# TINY1616.net
KiCad netlist of a schematic drawn in Altium Designer
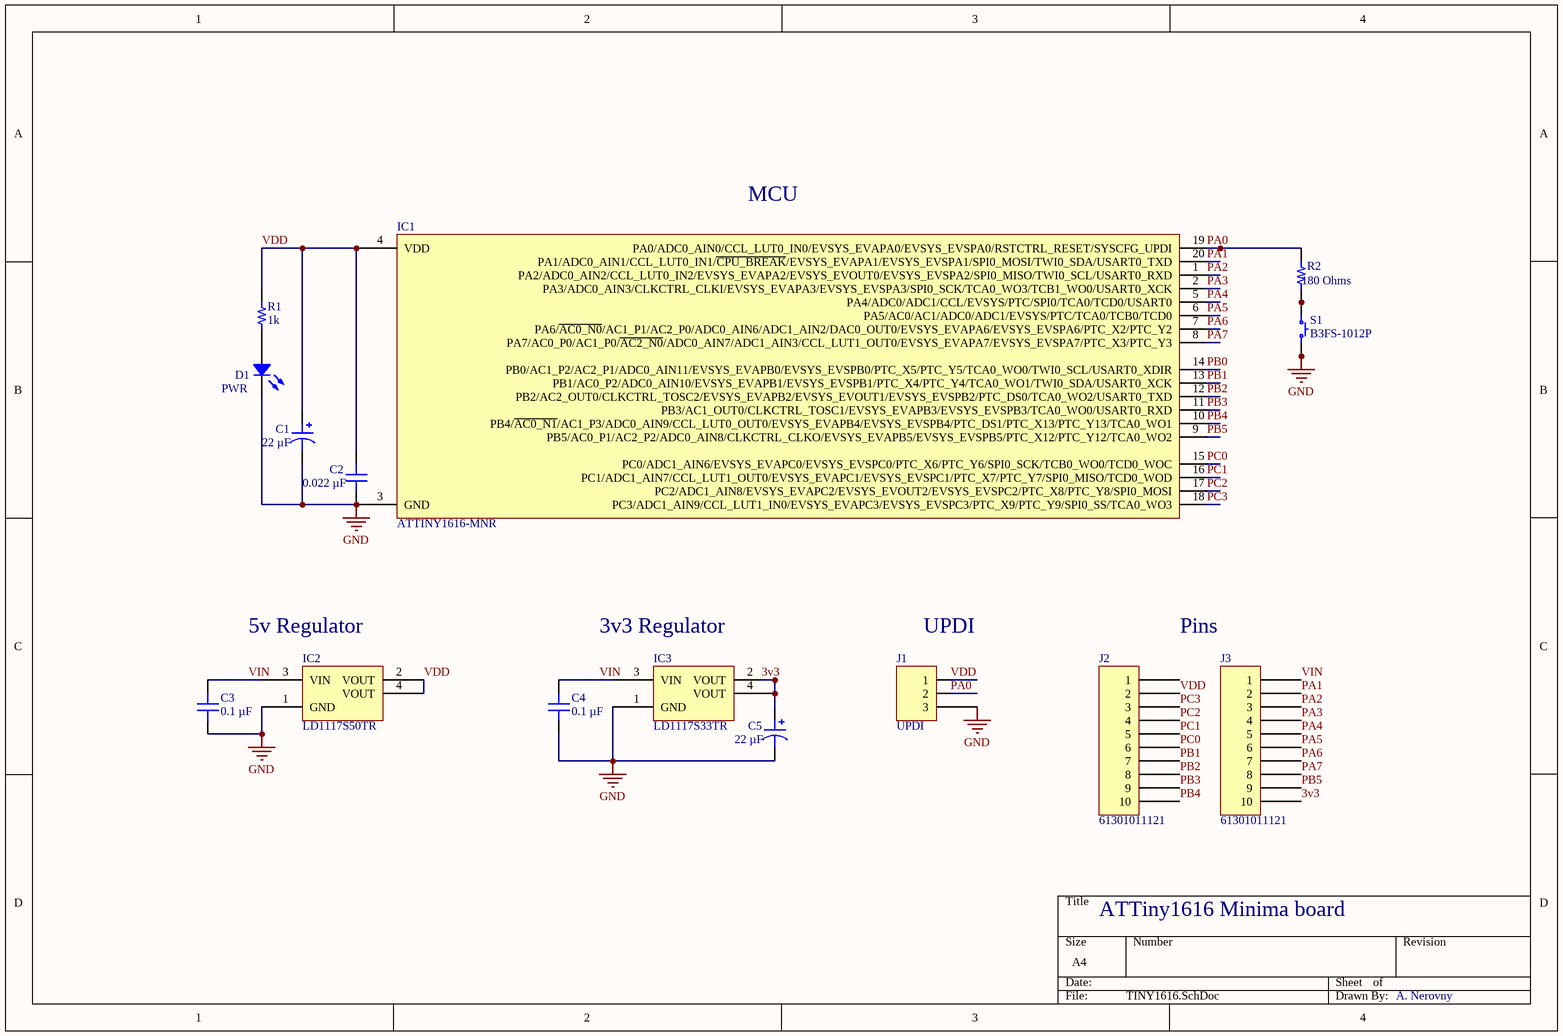
[diagram p0: TINY1616.SchDoc]

(export (version "E")
  (design (tool "Eeschema 10.0.6"))
  (components
    (comp (ref "C1")
      (value "22 µF")
      (footprint "CAP POL 1206_3216")
      (description "293D105X9016A8T")
      (fields (field (name "MANUFACTURER") "Vishay Sprague") (field (name "TOLERANCE") "±10%"))
      (libsource (lib "Celestial Altium Library - altium_library") (part "Polarised Capacitor"))
    )
    (comp (ref "C2")
      (value "0.022 µF")
      (footprint "CAP 0402_1005")
      (description "CAP CER 0402 22NF 50V X7R 10%")
      (fields
        (field (name "PART NUMBER") "C0402C223K5RECAUTO")
        (field (name "CAPACITANCE") "0.022 µF")
        (field (name "MANUFACTURER") "KEMET")
      )
      (libsource (lib "Celestial Altium Library - altium_library") (part "Capacitor"))
    )
    (comp (ref "C3")
      (value "0.1 µF")
      (footprint "CAP 0603_1608")
      (description "CAP CER 0.1UF 50V X7R 0603")
      (fields
        (field (name "PART NUMBER") "C0603C104K5RAC7411")
        (field (name "CAPACITANCE") "0.1 µF")
        (field (name "MANUFACTURER") "KEMET")
      )
      (libsource (lib "Celestial Altium Library - altium_library") (part "Capacitor"))
    )
    (comp (ref "C4")
      (value "0.1 µF")
      (footprint "CAP 0603_1608")
      (description "CAP CER 0.1UF 50V X7R 0603")
      (fields
        (field (name "PART NUMBER") "C0603C104K5RAC7411")
        (field (name "CAPACITANCE") "0.1 µF")
        (field (name "MANUFACTURER") "KEMET")
      )
      (libsource (lib "Celestial Altium Library - altium_library") (part "Capacitor"))
    )
    (comp (ref "C5")
      (value "22 µF")
      (footprint "CAP POL 1206_3216")
      (description "293D105X9016A8T")
      (fields (field (name "MANUFACTURER") "Vishay Sprague") (field (name "TOLERANCE") "±10%"))
      (libsource (lib "Celestial Altium Library - altium_library") (part "Polarised Capacitor"))
    )
    (comp (ref "D1")
      (value "PWR")
      (footprint "LED 0805_2012 GREEN")
      (description "LED GREEN CLEAR 0805 SMD")
      (fields
        (field (name "PART NUMBER") "QTLP630C4TR")
        (field (name "MANUFACTURER") "Everlight Electronics Co Ltd")
      )
      (libsource (lib "Celestial Altium Library - altium_library") (part "LED"))
    )
    (comp (ref "IC1")
      (value "ATTINY1616-MNR")
      (footprint "MICROCHIP VQFN-20 3X3 REB")
      (description "IC MCU 8BIT 16KB FLASH 20VQFN")
      (fields (field (name "MANUFACTURER") "Microchip Technology"))
      (libsource (lib "Celestial Altium Library - altium_library") (part "MICROCHIP ATTINY1616-MNR VQFN20"))
    )
    (comp (ref "IC2")
      (value "LD1117S50TR")
      (footprint "ST SOT-223")
      (description "IC REG LINEAR 5V 800MA SOT223")
      (fields (field (name "MANUFACTURER") "STMicroelectronics"))
      (libsource (lib "Celestial Altium Library - altium_library") (part "ST LD1117"))
    )
    (comp (ref "IC3")
      (value "LD1117S33TR")
      (footprint "ST SOT-223")
      (description "IC REG LINEAR 3.3V 800MA SOT223")
      (fields (field (name "MANUFACTURER") "STMicroelectronics"))
      (libsource (lib "Celestial Altium Library - altium_library") (part "ST LD1117"))
    )
    (comp (ref "J1")
      (value "UPDI")
      (footprint "WURTH WE-PHD 61300311121")
      (description "CONN HEADER VERT 3POS 2.54MM")
      (fields (field (name "PART NUMBER") "61300311121") (field (name "MANUFACTURER") "Würth Elektronik"))
      (libsource (lib "Celestial Altium Library - altium_library") (part "3 Pin"))
    )
    (comp (ref "J2")
      (value "61301011121")
      (footprint "WURTH WE-PHD 61301011121")
      (description "CONN HEADER VERT 10POS 2.54MM")
      (fields (field (name "MANUFACTURER") "Würth Elektronik"))
      (libsource (lib "Celestial Altium Library - altium_library") (part "10 Pin"))
    )
    (comp (ref "J3")
      (value "61301011121")
      (footprint "WURTH WE-PHD 61301011121")
      (description "CONN HEADER VERT 10POS 2.54MM")
      (fields (field (name "MANUFACTURER") "Würth Elektronik"))
      (libsource (lib "Celestial Altium Library - altium_library") (part "10 Pin"))
    )
    (comp (ref "R1")
      (value "1k")
      (footprint "RES 0402_1005")
      (description "RES 1K OHM 1% 1/5W 0402")
      (fields (field (name "PART NUMBER") "RCA04021K00FKEDHP") (field (name "MANUFACTURER") "Vishay Dale"))
      (libsource (lib "Celestial Altium Library - altium_library") (part "Resistor"))
    )
    (comp (ref "R2")
      (value "180 Ohms")
      (footprint "RES 0603_1608")
      (description "RES SMD 180 OHM 5% 1/10W 0603")
      (fields (field (name "PART NUMBER") "CRCW0603180RJNEA") (field (name "MANUFACTURER") "Vishay Dale"))
      (libsource (lib "Celestial Altium Library - altium_library") (part "Resistor"))
    )
    (comp (ref "S1")
      (value "B3FS-1012P")
      (footprint "OMRON B3FS-1012P")
      (description "SWITCH TACTILE SPST-NO 0.05A 24V")
      (fields (field (name "MANUFACTURER") "Omron Electronics Inc-EMC Div"))
      (libsource (lib "Celestial Altium Library - altium_library") (part "SPST-NO 4 PIN"))
    )
  )
  (nets
    (net (code "1") (name "/3v3") (class "Default")
      (node (ref "C5") (pin "1") (pinfunction "1_1") (pintype "passive"))
      (node (ref "IC3") (pin "2") (pinfunction "VOUT_2") (pintype "passive"))
      (node (ref "IC3") (pin "4") (pinfunction "VOUT_4") (pintype "passive"))
      (node (ref "J3") (pin "10") (pinfunction "10_10") (pintype "passive"))
    )
    (net (code "2") (name "/PA0") (class "Default")
      (node (ref "IC1") (pin "19") (pinfunction "PA0/ADC0_AIN0/CCL_LUT0_IN0/EVSYS_EVAPA0/EVSYS_EVSPA0/RSTCTRL_RESET/SYSCFG_UPDI_19") (pintype "passive"))
      (node (ref "J1") (pin "2") (pinfunction "2_2") (pintype "passive"))
      (node (ref "R2") (pin "2") (pinfunction "2_2") (pintype "passive"))
    )
    (net (code "3") (name "/PA1") (class "Default")
      (node (ref "IC1") (pin "20") (pinfunction "PA1/ADC0_AIN1/CCL_LUT0_IN1/~{CPU_BREAK}/EVSYS_EVAPA1/EVSYS_EVSPA1/SPI0_MOSI/TWI0_SDA/USART0_TXD_20") (pintype "passive"))
      (node (ref "J3") (pin "2") (pinfunction "2_2") (pintype "passive"))
    )
    (net (code "4") (name "/PA2") (class "Default")
      (node (ref "IC1") (pin "1") (pinfunction "PA2/ADC0_AIN2/CCL_LUT0_IN2/EVSYS_EVAPA2/EVSYS_EVOUT0/EVSYS_EVSPA2/SPI0_MISO/TWI0_SCL/USART0_RXD_1") (pintype "passive"))
      (node (ref "J3") (pin "3") (pinfunction "3_3") (pintype "passive"))
    )
    (net (code "5") (name "/PA3") (class "Default")
      (node (ref "IC1") (pin "2") (pinfunction "PA3/ADC0_AIN3/CLKCTRL_CLKI/EVSYS_EVAPA3/EVSYS_EVSPA3/SPI0_SCK/TCA0_WO3/TCB1_WO0/USART0_XCK_2") (pintype "passive"))
      (node (ref "J3") (pin "4") (pinfunction "4_4") (pintype "passive"))
    )
    (net (code "6") (name "/PA4") (class "Default")
      (node (ref "IC1") (pin "5") (pinfunction "PA4/ADC0/ADC1/CCL/EVSYS/PTC/SPI0/TCA0/TCD0/USART0_5") (pintype "passive"))
      (node (ref "J3") (pin "5") (pinfunction "5_5") (pintype "passive"))
    )
    (net (code "7") (name "/PA5") (class "Default")
      (node (ref "IC1") (pin "6") (pinfunction "PA5/AC0/AC1/ADC0/ADC1/EVSYS/PTC/TCA0/TCB0/TCD0_6") (pintype "passive"))
      (node (ref "J3") (pin "6") (pinfunction "6_6") (pintype "passive"))
    )
    (net (code "8") (name "/PA6") (class "Default")
      (node (ref "IC1") (pin "7") (pinfunction "PA6/~{AC0_N0}/AC1_P1/AC2_P0/ADC0_AIN6/ADC1_AIN2/DAC0_OUT0/EVSYS_EVAPA6/EVSYS_EVSPA6/PTC_X2/PTC_Y2_7") (pintype "passive"))
      (node (ref "J3") (pin "7") (pinfunction "7_7") (pintype "passive"))
    )
    (net (code "9") (name "/PA7") (class "Default")
      (node (ref "IC1") (pin "8") (pinfunction "PA7/AC0_P0/AC1_P0/~{AC2_N0}/ADC0_AIN7/ADC1_AIN3/CCL_LUT1_OUT0/EVSYS_EVAPA7/EVSYS_EVSPA7/PTC_X3/PTC_Y3_8") (pintype "passive"))
      (node (ref "J3") (pin "8") (pinfunction "8_8") (pintype "passive"))
    )
    (net (code "10") (name "/PB0") (class "Default")
      (node (ref "IC1") (pin "14") (pinfunction "PB0/AC1_P2/AC2_P1/ADC0_AIN11/EVSYS_EVAPB0/EVSYS_EVSPB0/PTC_X5/PTC_Y5/TCA0_WO0/TWI0_SCL/USART0_XDIR_14") (pintype "passive"))
    )
    (net (code "11") (name "/PB1") (class "Default")
      (node (ref "IC1") (pin "13") (pinfunction "PB1/AC0_P2/ADC0_AIN10/EVSYS_EVAPB1/EVSYS_EVSPB1/PTC_X4/PTC_Y4/TCA0_WO1/TWI0_SDA/USART0_XCK_13") (pintype "passive"))
      (node (ref "J2") (pin "7") (pinfunction "7_7") (pintype "passive"))
    )
    (net (code "12") (name "/PB2") (class "Default")
      (node (ref "IC1") (pin "12") (pinfunction "PB2/AC2_OUT0/CLKCTRL_TOSC2/EVSYS_EVAPB2/EVSYS_EVOUT1/EVSYS_EVSPB2/PTC_DS0/TCA0_WO2/USART0_TXD_12") (pintype "passive"))
      (node (ref "J2") (pin "8") (pinfunction "8_8") (pintype "passive"))
    )
    (net (code "13") (name "/PB3") (class "Default")
      (node (ref "IC1") (pin "11") (pinfunction "PB3/AC1_OUT0/CLKCTRL_TOSC1/EVSYS_EVAPB3/EVSYS_EVSPB3/TCA0_WO0/USART0_RXD_11") (pintype "passive"))
      (node (ref "J2") (pin "9") (pinfunction "9_9") (pintype "passive"))
    )
    (net (code "14") (name "/PB4") (class "Default")
      (node (ref "IC1") (pin "10") (pinfunction "PB4/~{AC0_N1}/AC1_P3/ADC0_AIN9/CCL_LUT0_OUT0/EVSYS_EVAPB4/EVSYS_EVSPB4/PTC_DS1/PTC_X13/PTC_Y13/TCA0_WO1_10") (pintype "passive"))
      (node (ref "J2") (pin "10") (pinfunction "10_10") (pintype "passive"))
    )
    (net (code "15") (name "/PB5") (class "Default")
      (node (ref "IC1") (pin "9") (pinfunction "PB5/AC0_P1/AC2_P2/ADC0_AIN8/CLKCTRL_CLKO/EVSYS_EVAPB5/EVSYS_EVSPB5/PTC_X12/PTC_Y12/TCA0_WO2_9") (pintype "passive"))
      (node (ref "J3") (pin "9") (pinfunction "9_9") (pintype "passive"))
    )
    (net (code "16") (name "/PC0") (class "Default")
      (node (ref "IC1") (pin "15") (pinfunction "PC0/ADC1_AIN6/EVSYS_EVAPC0/EVSYS_EVSPC0/PTC_X6/PTC_Y6/SPI0_SCK/TCB0_WO0/TCD0_WOC_15") (pintype "passive"))
      (node (ref "J2") (pin "6") (pinfunction "6_6") (pintype "passive"))
    )
    (net (code "17") (name "/PC1") (class "Default")
      (node (ref "IC1") (pin "16") (pinfunction "PC1/ADC1_AIN7/CCL_LUT1_OUT0/EVSYS_EVAPC1/EVSYS_EVSPC1/PTC_X7/PTC_Y7/SPI0_MISO/TCD0_WOD_16") (pintype "passive"))
      (node (ref "J2") (pin "5") (pinfunction "5_5") (pintype "passive"))
    )
    (net (code "18") (name "/PC2") (class "Default")
      (node (ref "IC1") (pin "17") (pinfunction "PC2/ADC1_AIN8/EVSYS_EVAPC2/EVSYS_EVOUT2/EVSYS_EVSPC2/PTC_X8/PTC_Y8/SPI0_MOSI_17") (pintype "passive"))
      (node (ref "J2") (pin "4") (pinfunction "4_4") (pintype "passive"))
    )
    (net (code "19") (name "/PC3") (class "Default")
      (node (ref "IC1") (pin "18") (pinfunction "PC3/ADC1_AIN9/CCL_LUT1_IN0/EVSYS_EVAPC3/EVSYS_EVSPC3/PTC_X9/PTC_Y9/SPI0_SS/TCA0_WO3_18") (pintype "passive"))
      (node (ref "J2") (pin "3") (pinfunction "3_3") (pintype "passive"))
    )
    (net (code "20") (name "/VDD") (class "Default")
      (node (ref "C1") (pin "1") (pinfunction "1_1") (pintype "passive"))
      (node (ref "C2") (pin "2") (pinfunction "2_2") (pintype "passive"))
      (node (ref "IC1") (pin "4") (pinfunction "VDD_4") (pintype "passive"))
      (node (ref "IC2") (pin "2") (pinfunction "VOUT_2") (pintype "passive"))
      (node (ref "IC2") (pin "4") (pinfunction "VOUT_4") (pintype "passive"))
      (node (ref "J1") (pin "1") (pinfunction "1_1") (pintype "passive"))
      (node (ref "J2") (pin "2") (pinfunction "2_2") (pintype "passive"))
      (node (ref "R1") (pin "2") (pinfunction "2_2") (pintype "passive"))
    )
    (net (code "21") (name "/VIN") (class "Default")
      (node (ref "C3") (pin "2") (pinfunction "2_2") (pintype "passive"))
      (node (ref "C4") (pin "2") (pinfunction "2_2") (pintype "passive"))
      (node (ref "IC2") (pin "3") (pinfunction "VIN_3") (pintype "passive"))
      (node (ref "IC3") (pin "3") (pinfunction "VIN_3") (pintype "passive"))
      (node (ref "J3") (pin "1") (pinfunction "1_1") (pintype "passive"))
    )
    (net (code "22") (name "GND") (class "Default")
      (node (ref "C1") (pin "2") (pinfunction "2_2") (pintype "passive"))
      (node (ref "C2") (pin "1") (pinfunction "1_1") (pintype "passive"))
      (node (ref "C3") (pin "1") (pinfunction "1_1") (pintype "passive"))
      (node (ref "C4") (pin "1") (pinfunction "1_1") (pintype "passive"))
      (node (ref "C5") (pin "2") (pinfunction "2_2") (pintype "passive"))
      (node (ref "D1") (pin "2") (pinfunction "2_2") (pintype "passive"))
      (node (ref "IC1") (pin "3") (pinfunction "GND_3") (pintype "passive"))
      (node (ref "IC2") (pin "1") (pinfunction "GND_1") (pintype "passive"))
      (node (ref "IC3") (pin "1") (pinfunction "GND_1") (pintype "passive"))
      (node (ref "J1") (pin "3") (pinfunction "3_3") (pintype "passive"))
      (node (ref "S1") (pin "3") (pinfunction "3_3") (pintype "passive"))
      (node (ref "S1") (pin "4") (pinfunction "4_4") (pintype "passive"))
    )
    (net (code "23") (name "Net-(D1-Pad1)") (class "Default")
      (node (ref "D1") (pin "1") (pinfunction "1_1") (pintype "passive"))
      (node (ref "R1") (pin "1") (pinfunction "1_1") (pintype "passive"))
    )
    (net (code "24") (name "Net-(R2-Pad1)") (class "Default")
      (node (ref "R2") (pin "1") (pinfunction "1_1") (pintype "passive"))
      (node (ref "S1") (pin "1") (pinfunction "1_1") (pintype "passive"))
      (node (ref "S1") (pin "2") (pinfunction "2_2") (pintype "passive"))
    )
    (net (code "25") (name "unconnected-(J2-Pad1)") (class "Default")
      (node (ref "J2") (pin "1") (pinfunction "1_1") (pintype "passive"))
    )
  )
)
